# controller17.net
KiCad netlist of a schematic drawn in EAGLE
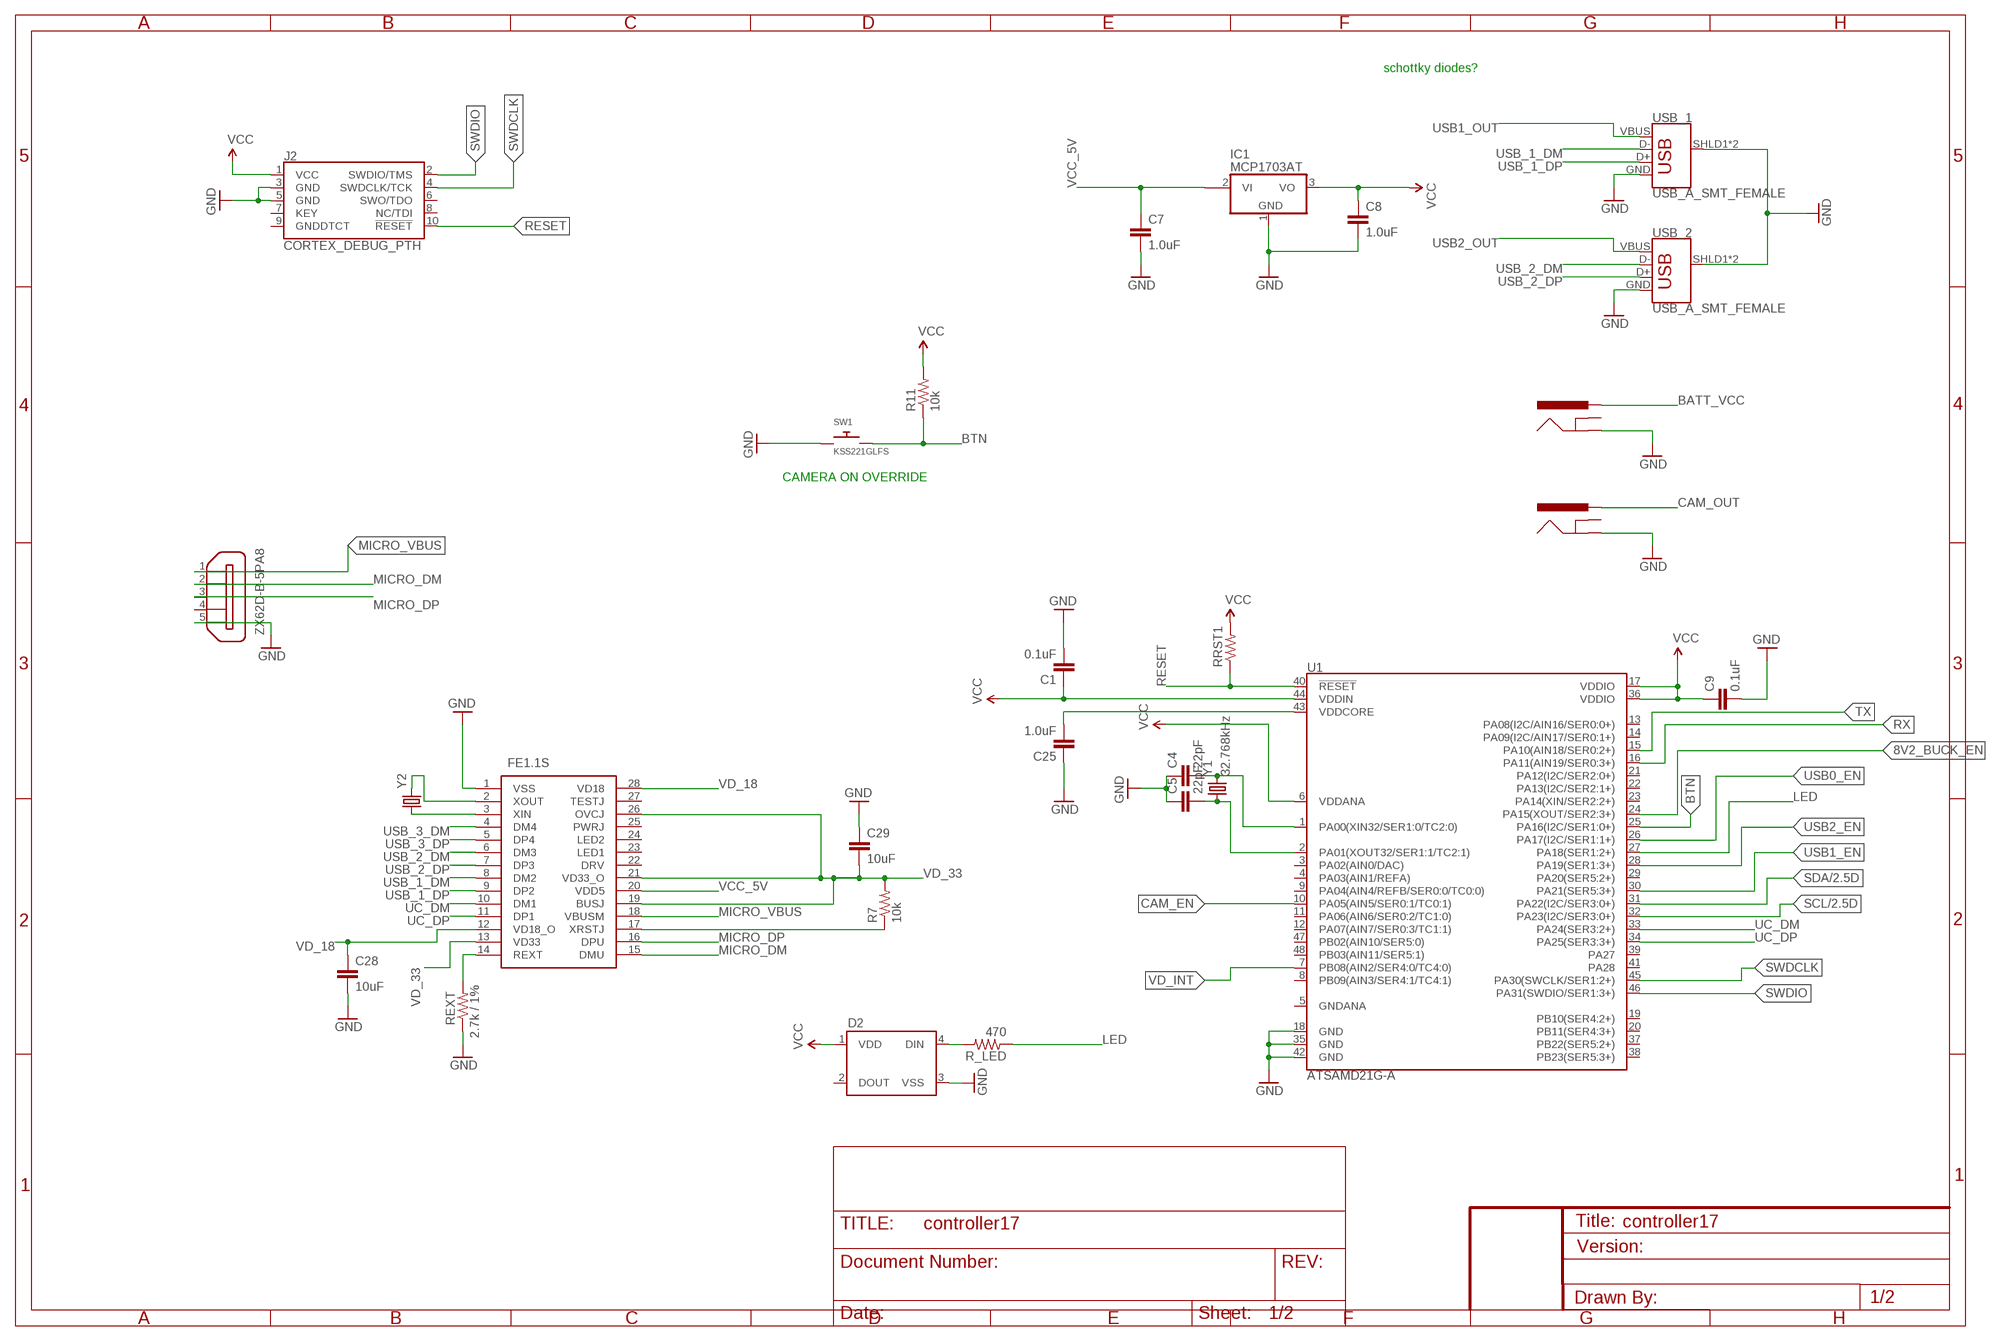
[diagram p0: schematic, sheet 1]
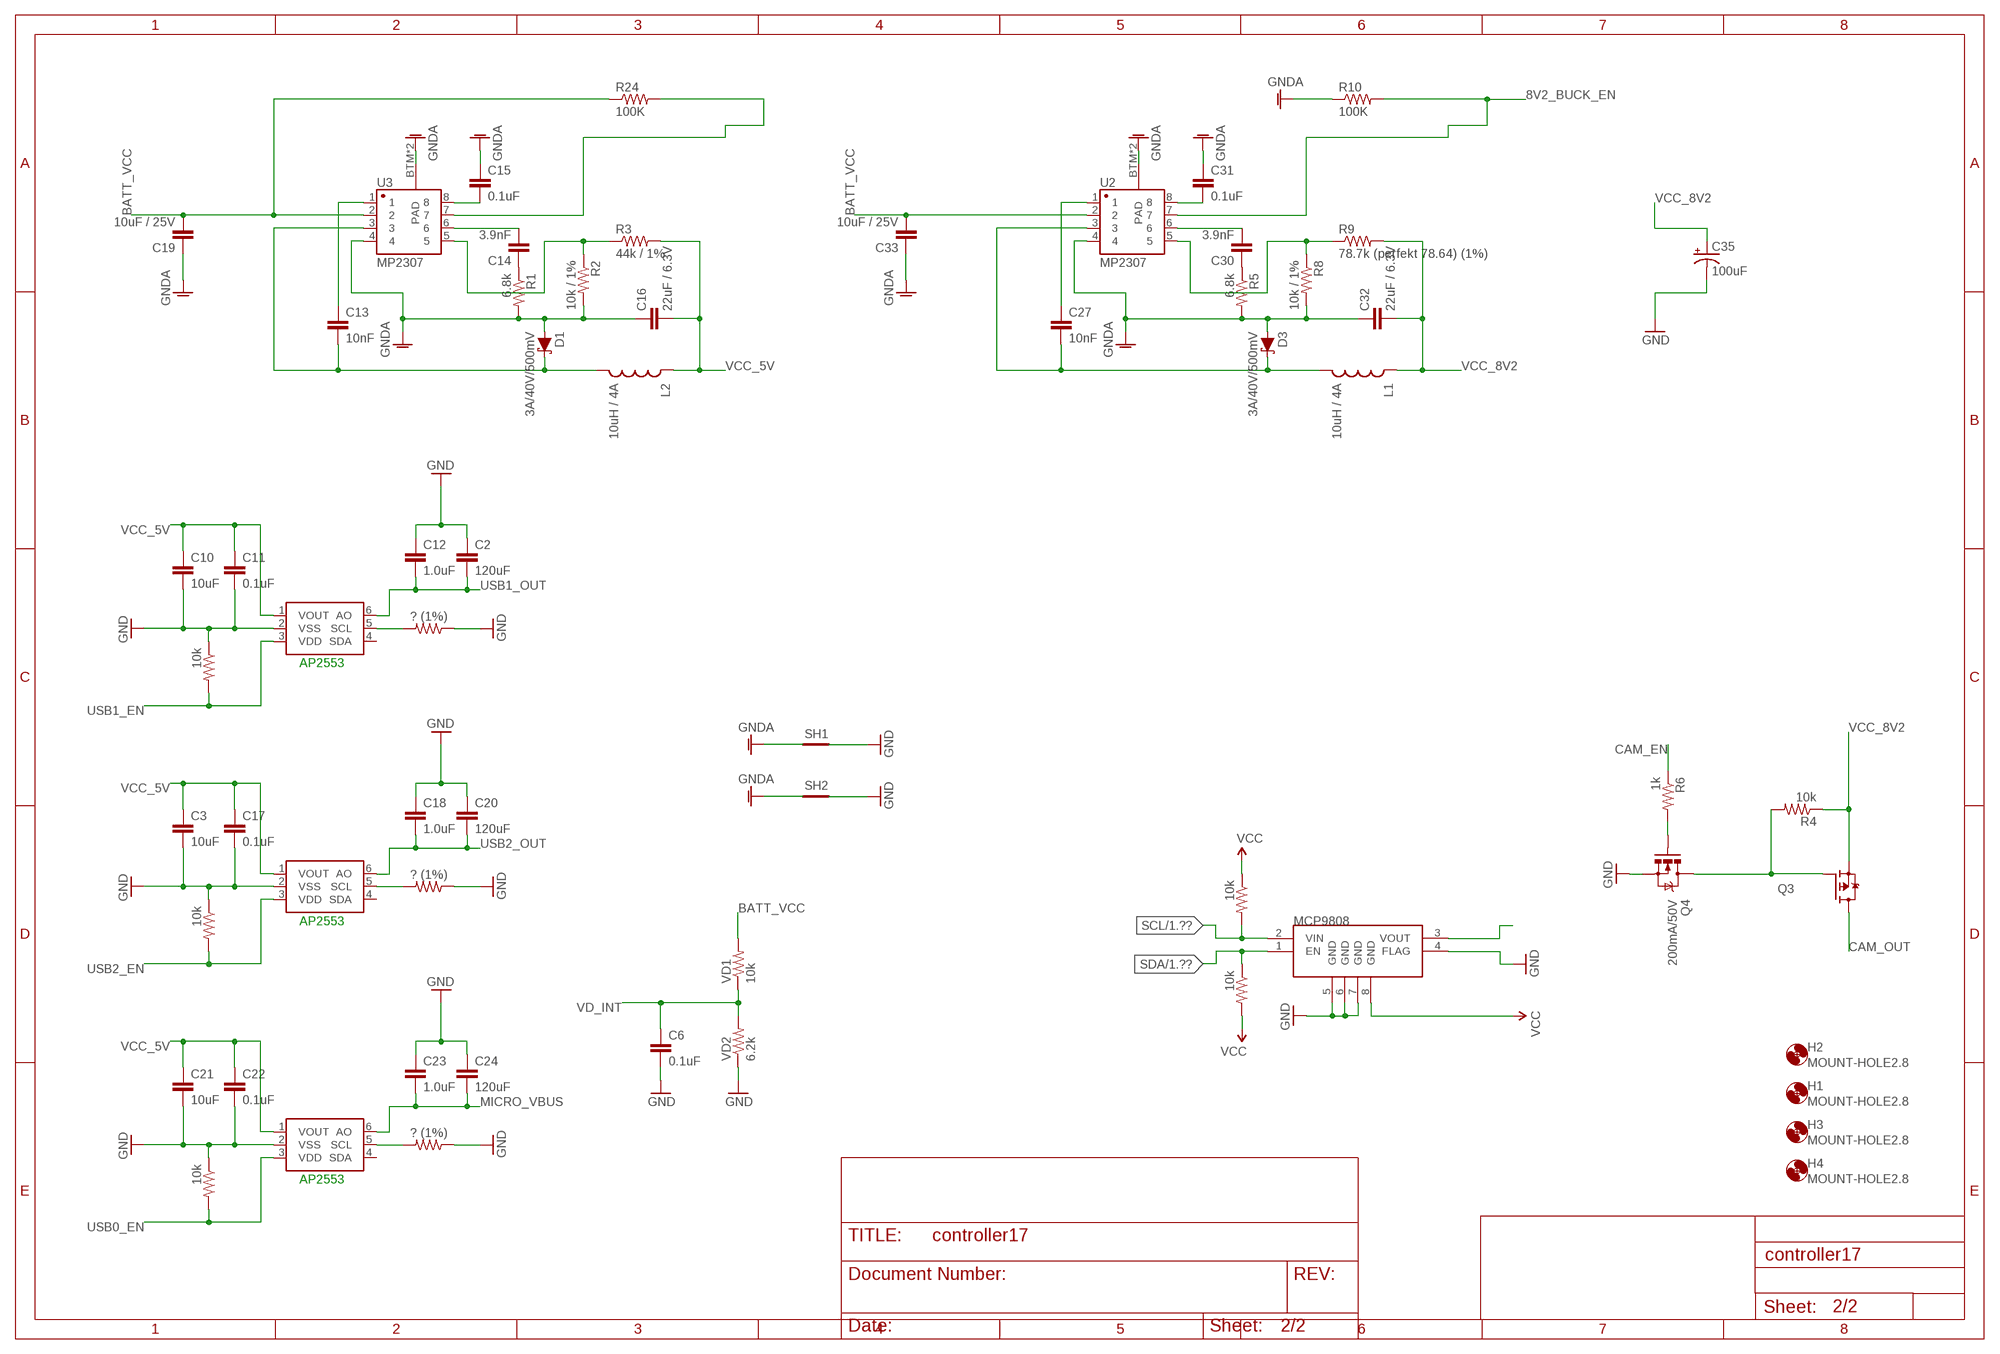
[diagram p1: schematic, sheet 2]

(export (version "E")
  (design (tool "Eeschema 10.0.6"))
  (components
    (comp (ref "AP1")
      (value "MCP4725")
      (footprint "eagle-import:SOT23-6")
      (libsource (lib "eagle-import") (part "MCP4725SOT-23"))
    )
    (comp (ref "AP2")
      (value "MCP4725")
      (footprint "eagle-import:SOT23-6")
      (libsource (lib "eagle-import") (part "MCP4725SOT-23"))
    )
    (comp (ref "AP2553")
      (value "MCP4725")
      (footprint "eagle-import:SOT23-6")
      (libsource (lib "eagle-import") (part "MCP4725SOT-23"))
    )
    (comp (ref "C2")
      (value "120uF")
      (footprint "eagle-import:1206")
      (libsource (lib "eagle-import") (part "1.0UF-1206-50V-10%"))
    )
    (comp (ref "C3")
      (value "10uF")
      (footprint "eagle-import:1206")
      (libsource (lib "eagle-import") (part "1.0UF-1206-50V-10%"))
    )
    (comp (ref "C6")
      (value "0.1uF")
      (footprint "eagle-import:1206")
      (libsource (lib "eagle-import") (part "CAP1206"))
    )
    (comp (ref "C10")
      (value "10uF")
      (footprint "eagle-import:1206")
      (libsource (lib "eagle-import") (part "1.0UF-1206-50V-10%"))
    )
    (comp (ref "C11")
      (value "0.1uF")
      (footprint "eagle-import:0805")
      (libsource (lib "eagle-import") (part "1.0UF-0805-25V-10%"))
    )
    (comp (ref "C12")
      (value "1.0uF")
      (footprint "eagle-import:0805")
      (libsource (lib "eagle-import") (part "1.0UF-0805-25V-10%"))
    )
    (comp (ref "C13")
      (value "10nF")
      (footprint "eagle-import:1206")
      (libsource (lib "eagle-import") (part "CAP1206"))
    )
    (comp (ref "C14")
      (value "3.9nF")
      (footprint "eagle-import:1206")
      (libsource (lib "eagle-import") (part "CAP1206"))
    )
    (comp (ref "C15")
      (value "0.1uF")
      (footprint "eagle-import:1206")
      (libsource (lib "eagle-import") (part "CAP1206"))
    )
    (comp (ref "C16")
      (value "22uF / 6.3V")
      (footprint "eagle-import:1210")
      (libsource (lib "eagle-import") (part "CAP1210"))
    )
    (comp (ref "C17")
      (value "0.1uF")
      (footprint "eagle-import:0805")
      (libsource (lib "eagle-import") (part "1.0UF-0805-25V-10%"))
    )
    (comp (ref "C18")
      (value "1.0uF")
      (footprint "eagle-import:1206")
      (libsource (lib "eagle-import") (part "1.0UF-1206-50V-10%"))
    )
    (comp (ref "C19")
      (value "10uF / 25V")
      (footprint "eagle-import:1210")
      (libsource (lib "eagle-import") (part "CAP1210"))
    )
    (comp (ref "C20")
      (value "120uF")
      (footprint "eagle-import:1206")
      (libsource (lib "eagle-import") (part "1.0UF-1206-50V-10%"))
    )
    (comp (ref "C21")
      (value "10uF")
      (footprint "eagle-import:1206")
      (libsource (lib "eagle-import") (part "1.0UF-1206-50V-10%"))
    )
    (comp (ref "C22")
      (value "0.1uF")
      (footprint "eagle-import:0805")
      (libsource (lib "eagle-import") (part "1.0UF-0805-25V-10%"))
    )
    (comp (ref "C23")
      (value "1.0uF")
      (footprint "eagle-import:1206")
      (libsource (lib "eagle-import") (part "1.0UF-1206-50V-10%"))
    )
    (comp (ref "C24")
      (value "120uF")
      (footprint "eagle-import:1206")
      (libsource (lib "eagle-import") (part "1.0UF-1206-50V-10%"))
    )
    (comp (ref "C27")
      (value "10nF")
      (footprint "eagle-import:1206")
      (libsource (lib "eagle-import") (part "CAP1206"))
    )
    (comp (ref "C30")
      (value "3.9nF")
      (footprint "eagle-import:1206")
      (libsource (lib "eagle-import") (part "CAP1206"))
    )
    (comp (ref "C31")
      (value "0.1uF")
      (footprint "eagle-import:1206")
      (libsource (lib "eagle-import") (part "CAP1206"))
    )
    (comp (ref "C32")
      (value "22uF / 6.3V")
      (footprint "eagle-import:1210")
      (libsource (lib "eagle-import") (part "CAP1210"))
    )
    (comp (ref "C33")
      (value "10uF / 25V")
      (footprint "eagle-import:1210")
      (libsource (lib "eagle-import") (part "CAP1210"))
    )
    (comp (ref "C35")
      (value "100uF")
      (footprint "eagle-import:PANASONIC_D")
      (libsource (lib "eagle-import") (part "100UF-POLAR-25V-20%(ELEC)"))
    )
    (comp (ref "D1")
      (value "3A/40V/500mV")
      (footprint "eagle-import:SMA-DIODE")
      (libsource (lib "eagle-import") (part "DIODE-SCHOTTKY-B340A"))
    )
    (comp (ref "D3")
      (value "3A/40V/500mV")
      (footprint "eagle-import:SMA-DIODE")
      (libsource (lib "eagle-import") (part "DIODE-SCHOTTKY-B340A"))
    )
    (comp (ref "H1")
      (value "MOUNT-HOLE2.8")
      (footprint "eagle-import:2,8")
      (libsource (lib "eagle-import") (part "MOUNT-HOLE2.8"))
    )
    (comp (ref "H2")
      (value "MOUNT-HOLE2.8")
      (footprint "eagle-import:2,8")
      (libsource (lib "eagle-import") (part "MOUNT-HOLE2.8"))
    )
    (comp (ref "H3")
      (value "MOUNT-HOLE2.8")
      (footprint "eagle-import:2,8")
      (libsource (lib "eagle-import") (part "MOUNT-HOLE2.8"))
    )
    (comp (ref "H4")
      (value "MOUNT-HOLE2.8")
      (footprint "eagle-import:2,8")
      (libsource (lib "eagle-import") (part "MOUNT-HOLE2.8"))
    )
    (comp (ref "L1")
      (value "10uH / 4A")
      (footprint "eagle-import:SRU1038")
      (libsource (lib "eagle-import") (part "INDUCTORSRU1038"))
    )
    (comp (ref "L2")
      (value "10uH / 4A")
      (footprint "eagle-import:SRU1038")
      (libsource (lib "eagle-import") (part "INDUCTORSRU1038"))
    )
    (comp (ref "MCP9808")
      (value "V_REG_MIC5216")
      (footprint "eagle-import:MSOP8")
      (libsource (lib "eagle-import") (part "V_REG_MIC5216"))
    )
    (comp (ref "Q3")
      (value "FDD4141TO252")
      (footprint "eagle-import:TO252")
      (libsource (lib "eagle-import") (part "FDD4141TO252"))
    )
    (comp (ref "Q4")
      (value "200mA/50V")
      (footprint "eagle-import:SOT23-3")
      (libsource (lib "eagle-import") (part "MOSFET-NCHANNELBSS138"))
    )
    (comp (ref "R1")
      (value "6.8k")
      (footprint "eagle-import:1206")
      (libsource (lib "eagle-import") (part "SparkFun-Resistors_RESISTOR1206"))
    )
    (comp (ref "R2")
      (value "10k / 1%")
      (footprint "eagle-import:1206")
      (libsource (lib "eagle-import") (part "SparkFun-Resistors_RESISTOR1206"))
    )
    (comp (ref "R3")
      (value "44k / 1%")
      (footprint "eagle-import:1206")
      (libsource (lib "eagle-import") (part "SparkFun-Resistors_RESISTOR1206"))
    )
    (comp (ref "R4")
      (value "10k")
      (footprint "eagle-import:0805")
      (libsource (lib "eagle-import") (part "SparkFun-Resistors_RESISTOR0805-RES"))
    )
    (comp (ref "R5")
      (value "6.8k")
      (footprint "eagle-import:1206")
      (libsource (lib "eagle-import") (part "SparkFun-Resistors_RESISTOR1206"))
    )
    (comp (ref "R6")
      (value "1k")
      (footprint "eagle-import:0805")
      (libsource (lib "eagle-import") (part "SparkFun-Resistors_RESISTOR0805-RES"))
    )
    (comp (ref "R8")
      (value "10k / 1%")
      (footprint "eagle-import:1206")
      (libsource (lib "eagle-import") (part "SparkFun-Resistors_RESISTOR1206"))
    )
    (comp (ref "R9")
      (value "78.7k (perfekt 78.64) (1%)")
      (footprint "eagle-import:1206")
      (libsource (lib "eagle-import") (part "SparkFun-Resistors_RESISTOR1206"))
    )
    (comp (ref "R10")
      (value "100K")
      (footprint "eagle-import:1206")
      (libsource (lib "eagle-import") (part "SparkFun-Resistors_RESISTOR1206"))
    )
    (comp (ref "R24")
      (value "100K")
      (footprint "eagle-import:1206")
      (libsource (lib "eagle-import") (part "SparkFun-Resistors_RESISTOR1206"))
    )
    (comp (ref "R_I2C_1")
      (value "10k")
      (footprint "eagle-import:0805")
      (libsource (lib "eagle-import") (part "RESISTOR0805-RES"))
    )
    (comp (ref "R_I2C_2")
      (value "10k")
      (footprint "eagle-import:0805")
      (libsource (lib "eagle-import") (part "RESISTOR0805-RES"))
    )
    (comp (ref "R_MOSFET_USB1")
      (value "? (1%)")
      (footprint "eagle-import:0805")
      (libsource (lib "eagle-import") (part "RESISTOR0805-RES"))
    )
    (comp (ref "R_MOSFET_USB2")
      (value "? (1%)")
      (footprint "eagle-import:0805")
      (libsource (lib "eagle-import") (part "RESISTOR0805-RES"))
    )
    (comp (ref "R_MOSFET_USB3")
      (value "10k")
      (footprint "eagle-import:0805")
      (libsource (lib "eagle-import") (part "RESISTOR0805-RES"))
    )
    (comp (ref "R_MOSFET_USB4")
      (value "10k")
      (footprint "eagle-import:0805")
      (libsource (lib "eagle-import") (part "RESISTOR0805-RES"))
    )
    (comp (ref "R_MOSFET_USB5")
      (value "? (1%)")
      (footprint "eagle-import:0805")
      (libsource (lib "eagle-import") (part "RESISTOR0805-RES"))
    )
    (comp (ref "R_MOSFET_USB6")
      (value "10k")
      (footprint "eagle-import:0805")
      (libsource (lib "eagle-import") (part "RESISTOR0805-RES"))
    )
    (comp (ref "SH1")
      (value "SHORT-HT5")
      (footprint "eagle-import:SHORT_TOP-50")
      (libsource (lib "eagle-import") (part "SHORT-HT5"))
    )
    (comp (ref "SH2")
      (value "SHORT-HT5")
      (footprint "eagle-import:SHORT_TOP-50")
      (libsource (lib "eagle-import") (part "SHORT-HT5"))
    )
    (comp (ref "U2")
      (value "MP2307")
      (footprint "eagle-import:SO08")
      (libsource (lib "eagle-import") (part "GENERIC-SOIC8MSGEQ7N-FILTER"))
    )
    (comp (ref "U3")
      (value "MP2307")
      (footprint "eagle-import:SO08")
      (libsource (lib "eagle-import") (part "GENERIC-SOIC8MSGEQ7N-FILTER"))
    )
    (comp (ref "VD1")
      (value "10k")
      (footprint "eagle-import:1206")
      (libsource (lib "eagle-import") (part "RESISTOR1206"))
    )
    (comp (ref "VD2")
      (value "6.2k")
      (footprint "eagle-import:1206")
      (libsource (lib "eagle-import") (part "RESISTOR1206"))
    )
    (comp (ref "C1")
      (value "0.1uF")
      (footprint "eagle-import:0805")
      (libsource (lib "eagle-import") (part "1.0UF-0805-25V-10%"))
    )
    (comp (ref "C4")
      (value "22pF")
      (footprint "eagle-import:0805")
      (libsource (lib "eagle-import") (part "SparkFun-Passives_CAP0805"))
    )
    (comp (ref "C5")
      (value "22pF")
      (footprint "eagle-import:0805")
      (libsource (lib "eagle-import") (part "SparkFun-Passives_CAP0805"))
    )
    (comp (ref "C7")
      (value "1.0uF")
      (footprint "eagle-import:0805")
      (libsource (lib "eagle-import") (part "1.0UF-0805-25V-10%"))
    )
    (comp (ref "C8")
      (value "1.0uF")
      (footprint "eagle-import:1206")
      (libsource (lib "eagle-import") (part "1.0UF-1206-50V-10%"))
    )
    (comp (ref "C9")
      (value "0.1uF")
      (footprint "eagle-import:0805")
      (libsource (lib "eagle-import") (part "1.0UF-0805-25V-10%"))
    )
    (comp (ref "C25")
      (value "1.0uF")
      (footprint "eagle-import:0805")
      (libsource (lib "eagle-import") (part "1.0UF-0805-25V-10%"))
    )
    (comp (ref "C28")
      (value "10uF")
      (footprint "eagle-import:0805")
      (libsource (lib "eagle-import") (part "1.0UF-0805-25V-10%"))
    )
    (comp (ref "C29")
      (value "10uF")
      (footprint "eagle-import:0805")
      (libsource (lib "eagle-import") (part "1.0UF-0805-25V-10%"))
    )
    (comp (ref "D2")
      (value "WS2812B")
      (footprint "eagle-import:WS2812B")
      (libsource (lib "eagle-import") (part "WS2812B"))
    )
    (comp (ref "IC1")
      (value "MCP1703AT")
      (footprint "eagle-import:SOT89")
      (libsource (lib "eagle-import") (part "MCP1703MB12"))
    )
    (comp (ref "IC3")
      (value "FE1.1S")
      (footprint "eagle-import:SOP64P600X175-28N")
      (libsource (lib "eagle-import") (part "FE1.1S"))
    )
    (comp (ref "J2")
      (value "CORTEX_DEBUG_PTH")
      (footprint "eagle-import:2X5-PTH-1.27MM")
      (libsource (lib "eagle-import") (part "CORTEX_DEBUG_PTH"))
    )
    (comp (ref "J3")
      (value "POWER_JACKPTH_BREAD")
      (footprint "eagle-import:POWER_JACK_PTH_BREAD")
      (libsource (lib "eagle-import") (part "POWER_JACKPTH_BREAD"))
    )
    (comp (ref "J4")
      (value "POWER_JACKPTH_BREAD")
      (footprint "eagle-import:POWER_JACK_PTH_BREAD")
      (libsource (lib "eagle-import") (part "POWER_JACKPTH_BREAD"))
    )
    (comp (ref "R7")
      (value "10k")
      (footprint "eagle-import:0805")
      (libsource (lib "eagle-import") (part "RESISTOR0805-RES"))
    )
    (comp (ref "R11")
      (value "10k")
      (footprint "eagle-import:0805")
      (libsource (lib "eagle-import") (part "RESISTOR0805-RES"))
    )
    (comp (ref "REXT")
      (value "2.7k / 1%")
      (footprint "eagle-import:0805")
      (libsource (lib "eagle-import") (part "RESISTOR0805-RES"))
    )
    (comp (ref "RRST1")
      (value "RESISTOR0805-RES")
      (footprint "eagle-import:0805")
      (libsource (lib "eagle-import") (part "RESISTOR0805-RES"))
    )
    (comp (ref "R_LED")
      (value "470")
      (footprint "eagle-import:0805")
      (libsource (lib "eagle-import") (part "SparkFun-Resistors_RESISTOR0805-RES"))
    )
    (comp (ref "SW1")
      (value "KSS221GLFS")
      (footprint "eagle-import:BTN_CK_KSS")
      (libsource (lib "eagle-import") (part "SWITCH_PUSHBUTTONC&K_KSS"))
    )
    (comp (ref "U1")
      (value "ATSAMD21G-A")
      (footprint "eagle-import:TQFP-48")
      (libsource (lib "eagle-import") (part "ATSAMD21G-A"))
    )
    (comp (ref "USB_1")
      (value "USB_A_SMT_FEMALE")
      (footprint "eagle-import:USB-A-S-SILK-FEMALE")
      (libsource (lib "eagle-import") (part "USB_A_SMT_FEMALE"))
    )
    (comp (ref "USB_2")
      (value "USB_A_SMT_FEMALE")
      (footprint "eagle-import:USB-A-S-SILK-FEMALE")
      (libsource (lib "eagle-import") (part "USB_A_SMT_FEMALE"))
    )
    (comp (ref "X2")
      (value "ZX62D-B-5PA8")
      (footprint "eagle-import:ZX62D-B-5PA8")
      (fields (field (name "MF") "Hirose"))
      (libsource (lib "eagle-import") (part "ZX62D-B-5PA8"))
    )
    (comp (ref "Y1")
      (value "32.768kHz")
      (footprint "eagle-import:CRYSTAL-SMD-3.2X1.5MM")
      (libsource (lib "eagle-import") (part "CRYSTAL3.2X1.5MM"))
    )
    (comp (ref "Y2")
      (value "12MHz")
      (footprint "eagle-import:CRYSTAL-SMD-5X3")
      (libsource (lib "eagle-import") (part "CRYSTALCRYSTAL-SMD-5X3-12MHZ"))
    )
  )
  (nets
    (net (code "1") (name "8V2_BUCK_EN") (class "Default")
      (node (ref "R10") (pin "2") (pinfunction "2_2") (pintype "passive"))
      (node (ref "U1") (pin "24") (pinfunction "PA15(XOUT/SER2:3+)_24") (pintype "bidirectional"))
      (node (ref "U2") (pin "7") (pinfunction "7_7") (pintype "bidirectional"))
    )
    (net (code "2") (name "BATT_VCC") (class "Default")
      (node (ref "C19") (pin "2") (pinfunction "2_2") (pintype "passive"))
      (node (ref "C33") (pin "2") (pinfunction "2_2") (pintype "passive"))
      (node (ref "J4") (pin "PWR") (pinfunction "PWR_PWR") (pintype "bidirectional"))
      (node (ref "R24") (pin "1") (pinfunction "1_1") (pintype "passive"))
      (node (ref "U2") (pin "2") (pinfunction "2_2") (pintype "bidirectional"))
      (node (ref "U3") (pin "2") (pinfunction "2_2") (pintype "bidirectional"))
      (node (ref "VD1") (pin "2") (pinfunction "2_2") (pintype "passive"))
    )
    (net (code "3") (name "BTN") (class "Default")
      (node (ref "R11") (pin "1") (pinfunction "1_1") (pintype "passive"))
      (node (ref "SW1") (pin "P$2") (pinfunction "P$2_P$2") (pintype "passive"))
      (node (ref "U1") (pin "25") (pinfunction "PA16(I2C/SER1:0+)_25") (pintype "bidirectional"))
    )
    (net (code "4") (name "CAM_EN") (class "Default")
      (node (ref "R6") (pin "1") (pinfunction "1_1") (pintype "passive"))
      (node (ref "U1") (pin "10") (pinfunction "PA05(AIN5/SER0:1/TC0:1)_10") (pintype "bidirectional"))
    )
    (net (code "5") (name "CAM_OUT") (class "Default")
      (node (ref "J3") (pin "PWR") (pinfunction "PWR_PWR") (pintype "bidirectional"))
      (node (ref "Q3") (pin "3") (pinfunction "D_3") (pintype "passive"))
    )
    (net (code "6") (name "GND") (class "Default")
      (node (ref "AP1") (pin "2") (pinfunction "VSS_2") (pintype "bidirectional"))
      (node (ref "AP2") (pin "2") (pinfunction "VSS_2") (pintype "bidirectional"))
      (node (ref "AP2553") (pin "2") (pinfunction "VSS_2") (pintype "bidirectional"))
      (node (ref "C1") (pin "2") (pinfunction "2_2") (pintype "passive"))
      (node (ref "C10") (pin "2") (pinfunction "2_2") (pintype "passive"))
      (node (ref "C11") (pin "2") (pinfunction "2_2") (pintype "passive"))
      (node (ref "C12") (pin "1") (pinfunction "1_1") (pintype "passive"))
      (node (ref "C17") (pin "2") (pinfunction "2_2") (pintype "passive"))
      (node (ref "C18") (pin "1") (pinfunction "1_1") (pintype "passive"))
      (node (ref "C2") (pin "1") (pinfunction "1_1") (pintype "passive"))
      (node (ref "C20") (pin "1") (pinfunction "1_1") (pintype "passive"))
      (node (ref "C21") (pin "2") (pinfunction "2_2") (pintype "passive"))
      (node (ref "C22") (pin "2") (pinfunction "2_2") (pintype "passive"))
      (node (ref "C23") (pin "1") (pinfunction "1_1") (pintype "passive"))
      (node (ref "C24") (pin "1") (pinfunction "1_1") (pintype "passive"))
      (node (ref "C25") (pin "1") (pinfunction "1_1") (pintype "passive"))
      (node (ref "C28") (pin "2") (pinfunction "2_2") (pintype "passive"))
      (node (ref "C29") (pin "1") (pinfunction "1_1") (pintype "passive"))
      (node (ref "C3") (pin "2") (pinfunction "2_2") (pintype "passive"))
      (node (ref "C35") (pin "-") (pinfunction "-_-") (pintype "passive"))
      (node (ref "C4") (pin "1") (pinfunction "1_1") (pintype "passive"))
      (node (ref "C5") (pin "1") (pinfunction "1_1") (pintype "passive"))
      (node (ref "C6") (pin "2") (pinfunction "2_2") (pintype "passive"))
      (node (ref "C7") (pin "2") (pinfunction "2_2") (pintype "passive"))
      (node (ref "C8") (pin "2") (pinfunction "2_2") (pintype "passive"))
      (node (ref "C9") (pin "2") (pinfunction "2_2") (pintype "passive"))
      (node (ref "D2") (pin "3") (pinfunction "VSS_3") (pintype "power_in"))
      (node (ref "IC1") (pin "1") (pinfunction "GND_1") (pintype "passive"))
      (node (ref "IC3") (pin "1") (pinfunction "VSS_1") (pintype "bidirectional"))
      (node (ref "J2") (pin "3") (pinfunction "GND_3") (pintype "bidirectional"))
      (node (ref "J2") (pin "5") (pinfunction "GND_5") (pintype "bidirectional"))
      (node (ref "J3") (pin "GND") (pinfunction "GND_GND") (pintype "bidirectional"))
      (node (ref "J4") (pin "GND") (pinfunction "GND_GND") (pintype "bidirectional"))
      (node (ref "MCP9808") (pin "4") (pinfunction "FLAG_4") (pintype "bidirectional"))
      (node (ref "MCP9808") (pin "5") (pinfunction "GND_5") (pintype "bidirectional"))
      (node (ref "MCP9808") (pin "6") (pinfunction "GND_6") (pintype "bidirectional"))
      (node (ref "MCP9808") (pin "7") (pinfunction "GND_7") (pintype "bidirectional"))
      (node (ref "Q4") (pin "2") (pinfunction "S_2") (pintype "passive"))
      (node (ref "REXT") (pin "1") (pinfunction "1_1") (pintype "passive"))
      (node (ref "R_MOSFET_USB1") (pin "1") (pinfunction "1_1") (pintype "passive"))
      (node (ref "R_MOSFET_USB2") (pin "1") (pinfunction "1_1") (pintype "passive"))
      (node (ref "R_MOSFET_USB3") (pin "1") (pinfunction "1_1") (pintype "passive"))
      (node (ref "R_MOSFET_USB4") (pin "1") (pinfunction "1_1") (pintype "passive"))
      (node (ref "R_MOSFET_USB5") (pin "1") (pinfunction "1_1") (pintype "passive"))
      (node (ref "R_MOSFET_USB6") (pin "1") (pinfunction "1_1") (pintype "passive"))
      (node (ref "SH1") (pin "2") (pinfunction "P$2_2") (pintype "bidirectional"))
      (node (ref "SH2") (pin "2") (pinfunction "P$2_2") (pintype "bidirectional"))
      (node (ref "SW1") (pin "P$1") (pinfunction "P$1_P$1") (pintype "passive"))
      (node (ref "U1") (pin "18") (pinfunction "GND_18") (pintype "bidirectional"))
      (node (ref "U1") (pin "35") (pinfunction "GND_35") (pintype "bidirectional"))
      (node (ref "U1") (pin "42") (pinfunction "GND_42") (pintype "bidirectional"))
      (node (ref "USB_1") (pin "GND") (pinfunction "GND_GND") (pintype "power_in"))
      (node (ref "USB_1") (pin "SHLD1") (pinfunction "SHIELD_SHLD1") (pintype "bidirectional"))
      (node (ref "USB_1") (pin "SHLD2") (pinfunction "SHIELD_SHLD2") (pintype "bidirectional"))
      (node (ref "USB_2") (pin "GND") (pinfunction "GND_GND") (pintype "power_in"))
      (node (ref "USB_2") (pin "SHLD1") (pinfunction "SHIELD_SHLD1") (pintype "bidirectional"))
      (node (ref "USB_2") (pin "SHLD2") (pinfunction "SHIELD_SHLD2") (pintype "bidirectional"))
      (node (ref "VD2") (pin "1") (pinfunction "1_1") (pintype "passive"))
      (node (ref "X2") (pin "5") (pinfunction "5_5") (pintype "passive"))
    )
    (net (code "7") (name "GNDA") (class "Default")
      (node (ref "C15") (pin "1") (pinfunction "1_1") (pintype "passive"))
      (node (ref "C16") (pin "1") (pinfunction "1_1") (pintype "passive"))
      (node (ref "C19") (pin "1") (pinfunction "1_1") (pintype "passive"))
      (node (ref "C31") (pin "1") (pinfunction "1_1") (pintype "passive"))
      (node (ref "C32") (pin "1") (pinfunction "1_1") (pintype "passive"))
      (node (ref "C33") (pin "1") (pinfunction "1_1") (pintype "passive"))
      (node (ref "D1") (pin "A") (pinfunction "A_A") (pintype "passive"))
      (node (ref "D3") (pin "A") (pinfunction "A_A") (pintype "passive"))
      (node (ref "R1") (pin "2") (pinfunction "2_2") (pintype "passive"))
      (node (ref "R10") (pin "1") (pinfunction "1_1") (pintype "passive"))
      (node (ref "R2") (pin "2") (pinfunction "2_2") (pintype "passive"))
      (node (ref "R5") (pin "2") (pinfunction "2_2") (pintype "passive"))
      (node (ref "R8") (pin "2") (pinfunction "2_2") (pintype "passive"))
      (node (ref "SH1") (pin "1") (pinfunction "P$1_1") (pintype "bidirectional"))
      (node (ref "SH2") (pin "1") (pinfunction "P$1_1") (pintype "bidirectional"))
      (node (ref "U2") (pin "4") (pinfunction "4_4") (pintype "bidirectional"))
      (node (ref "U2") (pin "BTM") (pinfunction "PAD_BTM") (pintype "bidirectional"))
      (node (ref "U2") (pin "P$1") (pinfunction "PAD_P$1") (pintype "bidirectional"))
      (node (ref "U3") (pin "4") (pinfunction "4_4") (pintype "bidirectional"))
      (node (ref "U3") (pin "BTM") (pinfunction "PAD_BTM") (pintype "bidirectional"))
      (node (ref "U3") (pin "P$1") (pinfunction "PAD_P$1") (pintype "bidirectional"))
    )
    (net (code "8") (name "LED") (class "Default")
      (node (ref "R_LED") (pin "1") (pinfunction "1_1") (pintype "passive"))
      (node (ref "U1") (pin "27") (pinfunction "PA18(SER1:2+)_27") (pintype "bidirectional"))
    )
    (net (code "9") (name "MICRO_DM") (class "Default")
      (node (ref "IC3") (pin "15") (pinfunction "DMU_15") (pintype "bidirectional"))
      (node (ref "X2") (pin "2") (pinfunction "2_2") (pintype "passive"))
    )
    (net (code "10") (name "MICRO_DP") (class "Default")
      (node (ref "IC3") (pin "16") (pinfunction "DPU_16") (pintype "bidirectional"))
      (node (ref "X2") (pin "3") (pinfunction "3_3") (pintype "passive"))
    )
    (net (code "11") (name "MICRO_VBUS") (class "Default")
      (node (ref "AP2") (pin "6") (pinfunction "AO_6") (pintype "bidirectional"))
      (node (ref "C23") (pin "2") (pinfunction "2_2") (pintype "passive"))
      (node (ref "C24") (pin "2") (pinfunction "2_2") (pintype "passive"))
      (node (ref "IC3") (pin "18") (pinfunction "VBUSM_18") (pintype "bidirectional"))
      (node (ref "X2") (pin "1") (pinfunction "1_1") (pintype "passive"))
    )
    (net (code "12") (name "Net-(AP1-SCL)") (class "Default")
      (node (ref "AP1") (pin "5") (pinfunction "SCL_5") (pintype "bidirectional"))
      (node (ref "R_MOSFET_USB2") (pin "2") (pinfunction "2_2") (pintype "passive"))
    )
    (net (code "13") (name "Net-(AP2-SCL)") (class "Default")
      (node (ref "AP2") (pin "5") (pinfunction "SCL_5") (pintype "bidirectional"))
      (node (ref "R_MOSFET_USB5") (pin "2") (pinfunction "2_2") (pintype "passive"))
    )
    (net (code "14") (name "Net-(AP2553-SCL)") (class "Default")
      (node (ref "AP2553") (pin "5") (pinfunction "SCL_5") (pintype "bidirectional"))
      (node (ref "R_MOSFET_USB1") (pin "2") (pinfunction "2_2") (pintype "passive"))
    )
    (net (code "15") (name "Net-(C13-Pad1)") (class "Default")
      (node (ref "C13") (pin "1") (pinfunction "1_1") (pintype "passive"))
      (node (ref "U3") (pin "1") (pinfunction "1_1") (pintype "bidirectional"))
    )
    (net (code "16") (name "Net-(C13-Pad2)") (class "Default")
      (node (ref "C13") (pin "2") (pinfunction "2_2") (pintype "passive"))
      (node (ref "D1") (pin "C") (pinfunction "C_C") (pintype "passive"))
      (node (ref "L2") (pin "2") (pinfunction "2_2") (pintype "passive"))
      (node (ref "U3") (pin "3") (pinfunction "3_3") (pintype "bidirectional"))
    )
    (net (code "17") (name "Net-(C14-Pad1)") (class "Default")
      (node (ref "C14") (pin "1") (pinfunction "1_1") (pintype "passive"))
      (node (ref "R1") (pin "1") (pinfunction "1_1") (pintype "passive"))
    )
    (net (code "18") (name "Net-(C14-Pad2)") (class "Default")
      (node (ref "C14") (pin "2") (pinfunction "2_2") (pintype "passive"))
      (node (ref "U3") (pin "6") (pinfunction "6_6") (pintype "bidirectional"))
    )
    (net (code "19") (name "Net-(C15-Pad2)") (class "Default")
      (node (ref "C15") (pin "2") (pinfunction "2_2") (pintype "passive"))
      (node (ref "U3") (pin "8") (pinfunction "8_8") (pintype "bidirectional"))
    )
    (net (code "20") (name "Net-(C27-Pad1)") (class "Default")
      (node (ref "C27") (pin "1") (pinfunction "1_1") (pintype "passive"))
      (node (ref "U2") (pin "1") (pinfunction "1_1") (pintype "bidirectional"))
    )
    (net (code "21") (name "Net-(C27-Pad2)") (class "Default")
      (node (ref "C27") (pin "2") (pinfunction "2_2") (pintype "passive"))
      (node (ref "D3") (pin "C") (pinfunction "C_C") (pintype "passive"))
      (node (ref "L1") (pin "2") (pinfunction "2_2") (pintype "passive"))
      (node (ref "U2") (pin "3") (pinfunction "3_3") (pintype "bidirectional"))
    )
    (net (code "22") (name "Net-(C30-Pad1)") (class "Default")
      (node (ref "C30") (pin "1") (pinfunction "1_1") (pintype "passive"))
      (node (ref "R5") (pin "1") (pinfunction "1_1") (pintype "passive"))
    )
    (net (code "23") (name "Net-(C30-Pad2)") (class "Default")
      (node (ref "C30") (pin "2") (pinfunction "2_2") (pintype "passive"))
      (node (ref "U2") (pin "6") (pinfunction "6_6") (pintype "bidirectional"))
    )
    (net (code "24") (name "Net-(C31-Pad2)") (class "Default")
      (node (ref "C31") (pin "2") (pinfunction "2_2") (pintype "passive"))
      (node (ref "U2") (pin "8") (pinfunction "8_8") (pintype "bidirectional"))
    )
    (net (code "25") (name "Net-(D2-DIN)") (class "Default")
      (node (ref "D2") (pin "4") (pinfunction "DIN_4") (pintype "input"))
      (node (ref "R_LED") (pin "2") (pinfunction "2_2") (pintype "passive"))
    )
    (net (code "26") (name "Net-(IC3-REXT)") (class "Default")
      (node (ref "IC3") (pin "14") (pinfunction "REXT_14") (pintype "bidirectional"))
      (node (ref "REXT") (pin "2") (pinfunction "2_2") (pintype "passive"))
    )
    (net (code "27") (name "Net-(IC3-XIN)") (class "Default")
      (node (ref "IC3") (pin "3") (pinfunction "XIN_3") (pintype "bidirectional"))
      (node (ref "Y2") (pin "1") (pinfunction "1_1") (pintype "passive"))
    )
    (net (code "28") (name "Net-(IC3-XOUT)") (class "Default")
      (node (ref "IC3") (pin "2") (pinfunction "XOUT_2") (pintype "bidirectional"))
      (node (ref "Y2") (pin "3") (pinfunction "2_3") (pintype "passive"))
    )
    (net (code "29") (name "Net-(IC3-XRSTJ)") (class "Default")
      (node (ref "IC3") (pin "17") (pinfunction "XRSTJ_17") (pintype "bidirectional"))
      (node (ref "R7") (pin "1") (pinfunction "1_1") (pintype "passive"))
    )
    (net (code "30") (name "Net-(Q3-G)") (class "Default")
      (node (ref "Q3") (pin "1") (pinfunction "G_1") (pintype "passive"))
      (node (ref "Q4") (pin "3") (pinfunction "D_3") (pintype "passive"))
      (node (ref "R4") (pin "2") (pinfunction "2_2") (pintype "passive"))
    )
    (net (code "31") (name "Net-(Q4-G)") (class "Default")
      (node (ref "Q4") (pin "1") (pinfunction "G_1") (pintype "passive"))
      (node (ref "R6") (pin "2") (pinfunction "2_2") (pintype "passive"))
    )
    (net (code "32") (name "Net-(R2-Pad1)") (class "Default")
      (node (ref "R2") (pin "1") (pinfunction "1_1") (pintype "passive"))
      (node (ref "R3") (pin "1") (pinfunction "1_1") (pintype "passive"))
      (node (ref "U3") (pin "5") (pinfunction "5_5") (pintype "bidirectional"))
    )
    (net (code "33") (name "Net-(R8-Pad1)") (class "Default")
      (node (ref "R8") (pin "1") (pinfunction "1_1") (pintype "passive"))
      (node (ref "R9") (pin "1") (pinfunction "1_1") (pintype "passive"))
      (node (ref "U2") (pin "5") (pinfunction "5_5") (pintype "bidirectional"))
    )
    (net (code "34") (name "Net-(R24-Pad2)") (class "Default")
      (node (ref "R24") (pin "2") (pinfunction "2_2") (pintype "passive"))
      (node (ref "U3") (pin "7") (pinfunction "7_7") (pintype "bidirectional"))
    )
    (net (code "35") (name "Net-(U1-PA00(XIN32{slash}SER1:0{slash}TC2:0))") (class "Default")
      (node (ref "C4") (pin "2") (pinfunction "2_2") (pintype "passive"))
      (node (ref "U1") (pin "1") (pinfunction "PA00(XIN32/SER1:0/TC2:0)_1") (pintype "bidirectional"))
      (node (ref "Y1") (pin "P$2") (pinfunction "2_P$2") (pintype "passive"))
    )
    (net (code "36") (name "Net-(U1-PA01(XOUT32{slash}SER1:1{slash}TC2:1))") (class "Default")
      (node (ref "C5") (pin "2") (pinfunction "2_2") (pintype "passive"))
      (node (ref "U1") (pin "2") (pinfunction "PA01(XOUT32/SER1:1/TC2:1)_2") (pintype "bidirectional"))
      (node (ref "Y1") (pin "P$1") (pinfunction "1_P$1") (pintype "passive"))
    )
    (net (code "37") (name "Net-(U1-VDDCORE)") (class "Default")
      (node (ref "C25") (pin "2") (pinfunction "2_2") (pintype "passive"))
      (node (ref "U1") (pin "43") (pinfunction "VDDCORE_43") (pintype "bidirectional"))
    )
    (net (code "38") (name "RESET") (class "Default")
      (node (ref "J2") (pin "10") (pinfunction "~{RESET}_10") (pintype "bidirectional"))
      (node (ref "RRST1") (pin "1") (pinfunction "1_1") (pintype "passive"))
      (node (ref "U1") (pin "40") (pinfunction "~{RESET}_40") (pintype "bidirectional"))
    )
    (net (code "39") (name "RX") (class "Default")
      (node (ref "U1") (pin "16") (pinfunction "PA11(AIN19/SER0:3+)_16") (pintype "bidirectional"))
    )
    (net (code "40") (name "SCL") (class "Default")
      (node (ref "MCP9808") (pin "2") (pinfunction "VIN_2") (pintype "bidirectional"))
      (node (ref "R_I2C_1") (pin "2") (pinfunction "2_2") (pintype "passive"))
      (node (ref "U1") (pin "32") (pinfunction "PA23(I2C/SER3:0+)_32") (pintype "bidirectional"))
    )
    (net (code "41") (name "SDA") (class "Default")
      (node (ref "MCP9808") (pin "1") (pinfunction "EN_1") (pintype "bidirectional"))
      (node (ref "R_I2C_2") (pin "1") (pinfunction "1_1") (pintype "passive"))
      (node (ref "U1") (pin "31") (pinfunction "PA22(I2C/SER3:0+)_31") (pintype "bidirectional"))
    )
    (net (code "42") (name "SWDCLK") (class "Default")
      (node (ref "J2") (pin "4") (pinfunction "SWDCLK/TCK_4") (pintype "bidirectional"))
      (node (ref "U1") (pin "45") (pinfunction "PA30(SWCLK/SER1:2+)_45") (pintype "bidirectional"))
    )
    (net (code "43") (name "SWDIO") (class "Default")
      (node (ref "J2") (pin "2") (pinfunction "SWDIO/TMS_2") (pintype "bidirectional"))
      (node (ref "U1") (pin "46") (pinfunction "PA31(SWDIO/SER1:3+)_46") (pintype "bidirectional"))
    )
    (net (code "44") (name "TX") (class "Default")
      (node (ref "U1") (pin "15") (pinfunction "PA10(AIN18/SER0:2+)_15") (pintype "bidirectional"))
    )
    (net (code "45") (name "UC_DM") (class "Default")
      (node (ref "IC3") (pin "10") (pinfunction "DM1_10") (pintype "bidirectional"))
      (node (ref "U1") (pin "33") (pinfunction "PA24(SER3:2+)_33") (pintype "bidirectional"))
    )
    (net (code "46") (name "UC_DP") (class "Default")
      (node (ref "IC3") (pin "11") (pinfunction "DP1_11") (pintype "bidirectional"))
      (node (ref "U1") (pin "34") (pinfunction "PA25(SER3:3+)_34") (pintype "bidirectional"))
    )
    (net (code "47") (name "USB0_EN") (class "Default")
      (node (ref "AP2") (pin "3") (pinfunction "VDD_3") (pintype "bidirectional"))
      (node (ref "R_MOSFET_USB6") (pin "2") (pinfunction "2_2") (pintype "passive"))
      (node (ref "U1") (pin "26") (pinfunction "PA17(I2C/SER1:1+)_26") (pintype "bidirectional"))
    )
    (net (code "48") (name "USB1_EN") (class "Default")
      (node (ref "AP2553") (pin "3") (pinfunction "VDD_3") (pintype "bidirectional"))
      (node (ref "R_MOSFET_USB3") (pin "2") (pinfunction "2_2") (pintype "passive"))
      (node (ref "U1") (pin "30") (pinfunction "PA21(SER5:3+)_30") (pintype "bidirectional"))
    )
    (net (code "49") (name "USB1_OUT") (class "Default")
      (node (ref "AP2553") (pin "6") (pinfunction "AO_6") (pintype "bidirectional"))
      (node (ref "C12") (pin "2") (pinfunction "2_2") (pintype "passive"))
      (node (ref "C2") (pin "2") (pinfunction "2_2") (pintype "passive"))
      (node (ref "USB_1") (pin "VBUS") (pinfunction "VBUS_VBUS") (pintype "power_in"))
    )
    (net (code "50") (name "USB2_EN") (class "Default")
      (node (ref "AP1") (pin "3") (pinfunction "VDD_3") (pintype "bidirectional"))
      (node (ref "R_MOSFET_USB4") (pin "2") (pinfunction "2_2") (pintype "passive"))
      (node (ref "U1") (pin "28") (pinfunction "PA19(SER1:3+)_28") (pintype "bidirectional"))
    )
    (net (code "51") (name "USB2_OUT") (class "Default")
      (node (ref "AP1") (pin "6") (pinfunction "AO_6") (pintype "bidirectional"))
      (node (ref "C18") (pin "2") (pinfunction "2_2") (pintype "passive"))
      (node (ref "C20") (pin "2") (pinfunction "2_2") (pintype "passive"))
      (node (ref "USB_2") (pin "VBUS") (pinfunction "VBUS_VBUS") (pintype "power_in"))
    )
    (net (code "52") (name "USB_1_DM") (class "Default")
      (node (ref "IC3") (pin "8") (pinfunction "DM2_8") (pintype "bidirectional"))
      (node (ref "USB_1") (pin "D-") (pinfunction "D-_D-") (pintype "bidirectional"))
    )
    (net (code "53") (name "USB_1_DP") (class "Default")
      (node (ref "IC3") (pin "9") (pinfunction "DP2_9") (pintype "bidirectional"))
      (node (ref "USB_1") (pin "D+") (pinfunction "D+_D+") (pintype "bidirectional"))
    )
    (net (code "54") (name "USB_2_DM") (class "Default")
      (node (ref "IC3") (pin "6") (pinfunction "DM3_6") (pintype "bidirectional"))
      (node (ref "USB_2") (pin "D-") (pinfunction "D-_D-") (pintype "bidirectional"))
    )
    (net (code "55") (name "USB_2_DP") (class "Default")
      (node (ref "IC3") (pin "7") (pinfunction "DP3_7") (pintype "bidirectional"))
      (node (ref "USB_2") (pin "D+") (pinfunction "D+_D+") (pintype "bidirectional"))
    )
    (net (code "56") (name "USB_3_DM") (class "Default")
      (node (ref "IC3") (pin "4") (pinfunction "DM4_4") (pintype "bidirectional"))
    )
    (net (code "57") (name "USB_3_DP") (class "Default")
      (node (ref "IC3") (pin "5") (pinfunction "DP4_5") (pintype "bidirectional"))
    )
    (net (code "58") (name "VCC") (class "Default")
      (node (ref "C1") (pin "1") (pinfunction "1_1") (pintype "passive"))
      (node (ref "C8") (pin "1") (pinfunction "1_1") (pintype "passive"))
      (node (ref "C9") (pin "1") (pinfunction "1_1") (pintype "passive"))
      (node (ref "D2") (pin "1") (pinfunction "VDD_1") (pintype "power_in"))
      (node (ref "IC1") (pin "3") (pinfunction "VO_3") (pintype "passive"))
      (node (ref "J2") (pin "1") (pinfunction "VCC_1") (pintype "bidirectional"))
      (node (ref "MCP9808") (pin "8") (pinfunction "GND_8") (pintype "bidirectional"))
      (node (ref "R11") (pin "2") (pinfunction "2_2") (pintype "passive"))
      (node (ref "RRST1") (pin "2") (pinfunction "2_2") (pintype "passive"))
      (node (ref "R_I2C_1") (pin "1") (pinfunction "1_1") (pintype "passive"))
      (node (ref "R_I2C_2") (pin "2") (pinfunction "2_2") (pintype "passive"))
      (node (ref "U1") (pin "17") (pinfunction "VDDIO_17") (pintype "bidirectional"))
      (node (ref "U1") (pin "36") (pinfunction "VDDIO_36") (pintype "bidirectional"))
      (node (ref "U1") (pin "44") (pinfunction "VDDIN_44") (pintype "bidirectional"))
      (node (ref "U1") (pin "6") (pinfunction "VDDANA_6") (pintype "bidirectional"))
    )
    (net (code "59") (name "VCC_5V") (class "Default")
      (node (ref "AP1") (pin "1") (pinfunction "VOUT_1") (pintype "bidirectional"))
      (node (ref "AP2") (pin "1") (pinfunction "VOUT_1") (pintype "bidirectional"))
      (node (ref "AP2553") (pin "1") (pinfunction "VOUT_1") (pintype "bidirectional"))
      (node (ref "C10") (pin "1") (pinfunction "1_1") (pintype "passive"))
      (node (ref "C11") (pin "1") (pinfunction "1_1") (pintype "passive"))
      (node (ref "C16") (pin "2") (pinfunction "2_2") (pintype "passive"))
      (node (ref "C17") (pin "1") (pinfunction "1_1") (pintype "passive"))
      (node (ref "C21") (pin "1") (pinfunction "1_1") (pintype "passive"))
      (node (ref "C22") (pin "1") (pinfunction "1_1") (pintype "passive"))
      (node (ref "C3") (pin "1") (pinfunction "1_1") (pintype "passive"))
      (node (ref "C7") (pin "1") (pinfunction "1_1") (pintype "passive"))
      (node (ref "IC1") (pin "2@1") (pinfunction "VI1_2@1") (pintype "input"))
      (node (ref "IC3") (pin "20") (pinfunction "VDD5_20") (pintype "bidirectional"))
      (node (ref "L2") (pin "1") (pinfunction "1_1") (pintype "passive"))
      (node (ref "R3") (pin "2") (pinfunction "2_2") (pintype "passive"))
    )
    (net (code "60") (name "VCC_8V2") (class "Default")
      (node (ref "C32") (pin "2") (pinfunction "2_2") (pintype "passive"))
      (node (ref "C35") (pin "+") (pinfunction "+_+") (pintype "passive"))
      (node (ref "L1") (pin "1") (pinfunction "1_1") (pintype "passive"))
      (node (ref "Q3") (pin "2") (pinfunction "S_2") (pintype "passive"))
      (node (ref "R4") (pin "1") (pinfunction "1_1") (pintype "passive"))
      (node (ref "R9") (pin "2") (pinfunction "2_2") (pintype "passive"))
    )
    (net (code "61") (name "VD_18") (class "Default")
      (node (ref "C28") (pin "1") (pinfunction "1_1") (pintype "passive"))
      (node (ref "IC3") (pin "12") (pinfunction "VD18_O_12") (pintype "bidirectional"))
      (node (ref "IC3") (pin "28") (pinfunction "VD18_28") (pintype "bidirectional"))
    )
    (net (code "62") (name "VD_33") (class "Default")
      (node (ref "C29") (pin "2") (pinfunction "2_2") (pintype "passive"))
      (node (ref "IC3") (pin "13") (pinfunction "VD33_13") (pintype "bidirectional"))
      (node (ref "IC3") (pin "19") (pinfunction "BUSJ_19") (pintype "bidirectional"))
      (node (ref "IC3") (pin "21") (pinfunction "VD33_O_21") (pintype "bidirectional"))
      (node (ref "IC3") (pin "26") (pinfunction "OVCJ_26") (pintype "bidirectional"))
      (node (ref "R7") (pin "2") (pinfunction "2_2") (pintype "passive"))
    )
    (net (code "63") (name "VD_INT") (class "Default")
      (node (ref "C6") (pin "1") (pinfunction "1_1") (pintype "passive"))
      (node (ref "U1") (pin "7") (pinfunction "PB08(AIN2/SER4:0/TC4:0)_7") (pintype "bidirectional"))
      (node (ref "VD1") (pin "1") (pinfunction "1_1") (pintype "passive"))
      (node (ref "VD2") (pin "2") (pinfunction "2_2") (pintype "passive"))
    )
    (net (code "64") (name "unconnected-(AP1-SDA-Pad4)") (class "Default")
      (node (ref "AP1") (pin "4") (pinfunction "SDA_4") (pintype "bidirectional"))
    )
    (net (code "65") (name "unconnected-(AP2-SDA-Pad4)") (class "Default")
      (node (ref "AP2") (pin "4") (pinfunction "SDA_4") (pintype "bidirectional"))
    )
    (net (code "66") (name "unconnected-(AP2553-SDA-Pad4)") (class "Default")
      (node (ref "AP2553") (pin "4") (pinfunction "SDA_4") (pintype "bidirectional"))
    )
    (net (code "67") (name "unconnected-(D2-DOUT-Pad2)") (class "Default")
      (node (ref "D2") (pin "2") (pinfunction "DOUT_2") (pintype "output"))
    )
    (net (code "68") (name "unconnected-(IC1-VI-Pad2)") (class "Default")
      (node (ref "IC1") (pin "2") (pinfunction "VI_2") (pintype "input"))
    )
    (net (code "69") (name "unconnected-(IC3-DRV-Pad22)") (class "Default")
      (node (ref "IC3") (pin "22") (pinfunction "DRV_22") (pintype "bidirectional"))
    )
    (net (code "70") (name "unconnected-(IC3-LED1-Pad23)") (class "Default")
      (node (ref "IC3") (pin "23") (pinfunction "LED1_23") (pintype "bidirectional"))
    )
    (net (code "71") (name "unconnected-(IC3-LED2-Pad24)") (class "Default")
      (node (ref "IC3") (pin "24") (pinfunction "LED2_24") (pintype "bidirectional"))
    )
    (net (code "72") (name "unconnected-(IC3-PWRJ-Pad25)") (class "Default")
      (node (ref "IC3") (pin "25") (pinfunction "PWRJ_25") (pintype "bidirectional"))
    )
    (net (code "73") (name "unconnected-(IC3-TESTJ-Pad27)") (class "Default")
      (node (ref "IC3") (pin "27") (pinfunction "TESTJ_27") (pintype "bidirectional"))
    )
    (net (code "74") (name "unconnected-(J2-GNDDTCT-Pad9)") (class "Default")
      (node (ref "J2") (pin "9") (pinfunction "GNDDTCT_9") (pintype "bidirectional"))
    )
    (net (code "75") (name "unconnected-(J2-KEY-Pad7)") (class "Default")
      (node (ref "J2") (pin "7") (pinfunction "KEY_7") (pintype "bidirectional"))
    )
    (net (code "76") (name "unconnected-(J2-NC{slash}TDI-Pad8)") (class "Default")
      (node (ref "J2") (pin "8") (pinfunction "NC/TDI_8") (pintype "bidirectional"))
    )
    (net (code "77") (name "unconnected-(J2-SWO{slash}TDO-Pad6)") (class "Default")
      (node (ref "J2") (pin "6") (pinfunction "SWO/TDO_6") (pintype "bidirectional"))
    )
    (net (code "78") (name "unconnected-(J3-PadGNDBREAK)") (class "Default")
      (node (ref "J3") (pin "GNDBREAK") (pinfunction "GNDBREAK_GNDBREAK") (pintype "bidirectional"))
    )
    (net (code "79") (name "unconnected-(J4-PadGNDBREAK)") (class "Default")
      (node (ref "J4") (pin "GNDBREAK") (pinfunction "GNDBREAK_GNDBREAK") (pintype "bidirectional"))
    )
    (net (code "80") (name "unconnected-(MCP9808-VOUT-Pad3)") (class "Default")
      (node (ref "MCP9808") (pin "3") (pinfunction "VOUT_3") (pintype "bidirectional"))
    )
    (net (code "81") (name "unconnected-(U1-GNDANA-Pad5)") (class "Default")
      (node (ref "U1") (pin "5") (pinfunction "GNDANA_5") (pintype "bidirectional"))
    )
    (net (code "82") (name "unconnected-(U1-PA02(AIN0{slash}DAC)-Pad3)") (class "Default")
      (node (ref "U1") (pin "3") (pinfunction "PA02(AIN0/DAC)_3") (pintype "bidirectional"))
    )
    (net (code "83") (name "unconnected-(U1-PA03(AIN1{slash}REFA)-Pad4)") (class "Default")
      (node (ref "U1") (pin "4") (pinfunction "PA03(AIN1/REFA)_4") (pintype "bidirectional"))
    )
    (net (code "84") (name "unconnected-(U1-PA04(AIN4{slash}REFB{slash}SER0:0{slash}TC0:0)-Pad9)") (class "Default")
      (node (ref "U1") (pin "9") (pinfunction "PA04(AIN4/REFB/SER0:0/TC0:0)_9") (pintype "bidirectional"))
    )
    (net (code "85") (name "unconnected-(U1-PA06(AIN6{slash}SER0:2{slash}TC1:0)-Pad11)") (class "Default")
      (node (ref "U1") (pin "11") (pinfunction "PA06(AIN6/SER0:2/TC1:0)_11") (pintype "bidirectional"))
    )
    (net (code "86") (name "unconnected-(U1-PA07(AIN7{slash}SER0:3{slash}TC1:1)-Pad12)") (class "Default")
      (node (ref "U1") (pin "12") (pinfunction "PA07(AIN7/SER0:3/TC1:1)_12") (pintype "bidirectional"))
    )
    (net (code "87") (name "unconnected-(U1-PA08(I2C{slash}AIN16{slash}SER0:0+)-Pad13)") (class "Default")
      (node (ref "U1") (pin "13") (pinfunction "PA08(I2C/AIN16/SER0:0+)_13") (pintype "bidirectional"))
    )
    (net (code "88") (name "unconnected-(U1-PA09(I2C{slash}AIN17{slash}SER0:1+)-Pad14)") (class "Default")
      (node (ref "U1") (pin "14") (pinfunction "PA09(I2C/AIN17/SER0:1+)_14") (pintype "bidirectional"))
    )
    (net (code "89") (name "unconnected-(U1-PA12(I2C{slash}SER2:0+)-Pad21)") (class "Default")
      (node (ref "U1") (pin "21") (pinfunction "PA12(I2C/SER2:0+)_21") (pintype "bidirectional"))
    )
    (net (code "90") (name "unconnected-(U1-PA13(I2C{slash}SER2:1+)-Pad22)") (class "Default")
      (node (ref "U1") (pin "22") (pinfunction "PA13(I2C/SER2:1+)_22") (pintype "bidirectional"))
    )
    (net (code "91") (name "unconnected-(U1-PA14(XIN{slash}SER2:2+)-Pad23)") (class "Default")
      (node (ref "U1") (pin "23") (pinfunction "PA14(XIN/SER2:2+)_23") (pintype "bidirectional"))
    )
    (net (code "92") (name "unconnected-(U1-PA20(SER5:2+)-Pad29)") (class "Default")
      (node (ref "U1") (pin "29") (pinfunction "PA20(SER5:2+)_29") (pintype "bidirectional"))
    )
    (net (code "93") (name "unconnected-(U1-PA27-Pad39)") (class "Default")
      (node (ref "U1") (pin "39") (pinfunction "PA27_39") (pintype "bidirectional"))
    )
    (net (code "94") (name "unconnected-(U1-PA28-Pad41)") (class "Default")
      (node (ref "U1") (pin "41") (pinfunction "PA28_41") (pintype "bidirectional"))
    )
    (net (code "95") (name "unconnected-(U1-PB02(AIN10{slash}SER5:0)-Pad47)") (class "Default")
      (node (ref "U1") (pin "47") (pinfunction "PB02(AIN10/SER5:0)_47") (pintype "bidirectional"))
    )
    (net (code "96") (name "unconnected-(U1-PB03(AIN11{slash}SER5:1)-Pad48)") (class "Default")
      (node (ref "U1") (pin "48") (pinfunction "PB03(AIN11/SER5:1)_48") (pintype "bidirectional"))
    )
    (net (code "97") (name "unconnected-(U1-PB09(AIN3{slash}SER4:1{slash}TC4:1)-Pad8)") (class "Default")
      (node (ref "U1") (pin "8") (pinfunction "PB09(AIN3/SER4:1/TC4:1)_8") (pintype "bidirectional"))
    )
    (net (code "98") (name "unconnected-(U1-PB10(SER4:2+)-Pad19)") (class "Default")
      (node (ref "U1") (pin "19") (pinfunction "PB10(SER4:2+)_19") (pintype "bidirectional"))
    )
    (net (code "99") (name "unconnected-(U1-PB11(SER4:3+)-Pad20)") (class "Default")
      (node (ref "U1") (pin "20") (pinfunction "PB11(SER4:3+)_20") (pintype "bidirectional"))
    )
    (net (code "100") (name "unconnected-(U1-PB22(SER5:2+)-Pad37)") (class "Default")
      (node (ref "U1") (pin "37") (pinfunction "PB22(SER5:2+)_37") (pintype "bidirectional"))
    )
    (net (code "101") (name "unconnected-(U1-PB23(SER5:3+)-Pad38)") (class "Default")
      (node (ref "U1") (pin "38") (pinfunction "PB23(SER5:3+)_38") (pintype "bidirectional"))
    )
    (net (code "102") (name "unconnected-(X2-Pad4)") (class "Default")
      (node (ref "X2") (pin "4") (pinfunction "4_4") (pintype "passive"))
    )
  )
)
